# main.net
KiCad netlist of a schematic drawn in Altium Designer
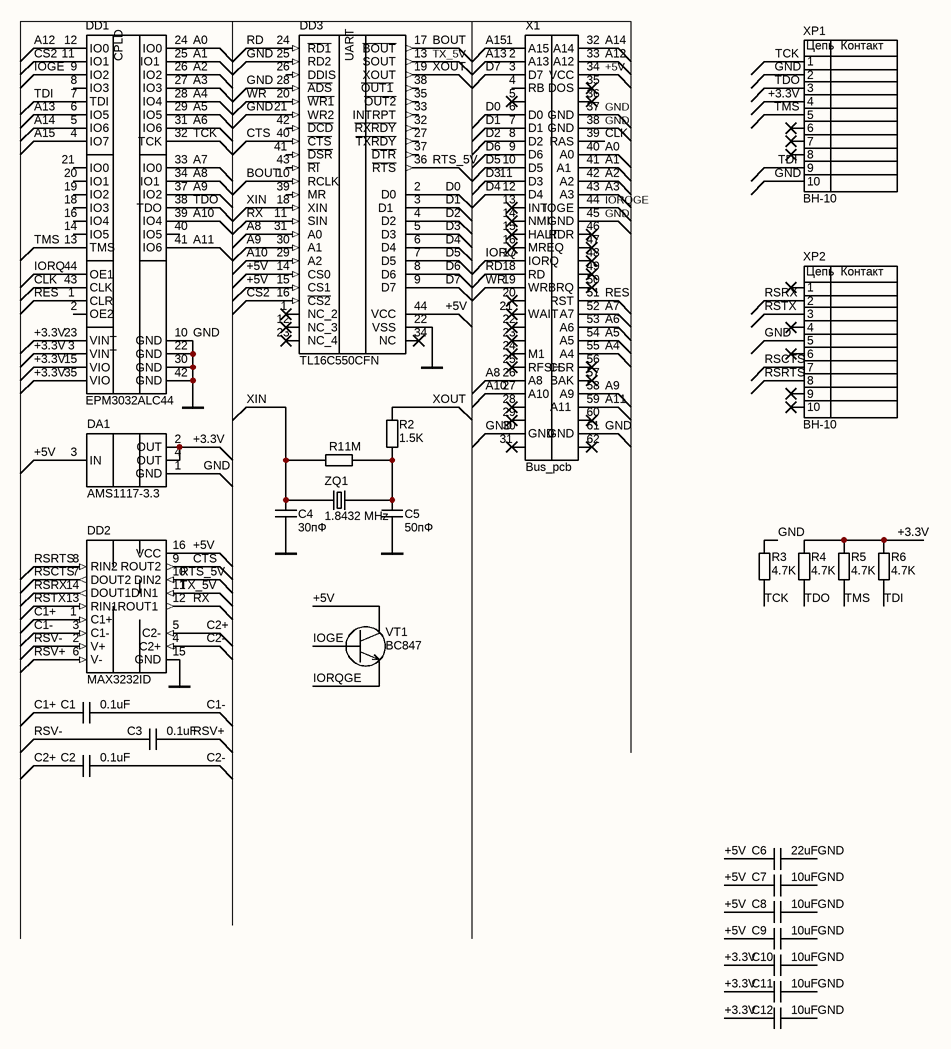
[diagram p0: main.SchDoc]

(export (version "E")
  (design (tool "Eeschema 10.0.6"))
  (components
    (comp (ref "C1") (value "0.1uF") (footprint "C0805") (libsource (lib "Capacitors") (part "CapCer")))
    (comp (ref "C2") (value "0.1uF") (footprint "C0805") (libsource (lib "Capacitors") (part "CapCer")))
    (comp (ref "C3") (value "0.1uF") (footprint "C0805") (libsource (lib "Capacitors") (part "CapCer")))
    (comp (ref "C4") (value "30пФ") (footprint "C0805") (libsource (lib "Capacitors") (part "CapCer")))
    (comp (ref "C5") (value "50пФ") (footprint "C0805") (libsource (lib "Capacitors") (part "CapCer")))
    (comp (ref "C6") (value "22uF") (footprint "С1206") (libsource (lib "Capacitors") (part "CapCer")))
    (comp (ref "C7") (value "10uF") (footprint "C0805") (libsource (lib "Capacitors") (part "CapCer")))
    (comp (ref "C8") (value "10uF") (footprint "C0805") (libsource (lib "Capacitors") (part "CapCer")))
    (comp (ref "C9") (value "10uF") (footprint "C0805") (libsource (lib "Capacitors") (part "CapCer")))
    (comp (ref "C10") (value "10uF") (footprint "C0805") (libsource (lib "Capacitors") (part "CapCer")))
    (comp (ref "C11") (value "10uF") (footprint "C0805") (libsource (lib "Capacitors") (part "CapCer")))
    (comp (ref "C12") (value "10uF") (footprint "C0805") (libsource (lib "Capacitors") (part "CapCer")))
    (comp (ref "DA1")
      (value "AMS1117-3.3")
      (footprint "SOT229P700X180-4N")
      (libsource (lib "LDO") (part "AMS1117-3.3"))
    )
    (comp (ref "DD1")
      (value "EPM3032ALC44")
      (footprint "PLCC-44-R")
      (description "44-Pin PLCC44")
      (libsource (lib "cpld") (part "EPM3032ALC44"))
    )
    (comp (ref "DD2")
      (value "MAX3232ID")
      (footprint "SOIC127P600X175-16N")
      (description "3-V to 5.5-V multichannel RS-232 line driver & receiver 16-SOIC -40 to 85")
      (fields (field (name "MF") "Texas Instruments"))
      (libsource (lib "Shifter") (part "MAX3232ID"))
    )
    (comp (ref "DD3")
      (value "TL16C550CFN")
      (footprint "PLCC-44-R")
      (description "ASYNCHRONOUS COMMUNICATIONS ELEMENT")
      (libsource (lib "uart") (part "TL16C550CFN"))
    )
    (comp (ref "R1") (value "1M") (footprint "R0805") (libsource (lib "Resistors") (part "Res")))
    (comp (ref "R2") (value "1.5K") (footprint "R0805") (libsource (lib "Resistors") (part "Res")))
    (comp (ref "R3") (value "4.7K") (footprint "R0805") (libsource (lib "Resistors") (part "Res")))
    (comp (ref "R4") (value "4.7K") (footprint "R0805") (libsource (lib "Resistors") (part "Res")))
    (comp (ref "R5") (value "4.7K") (footprint "R0805") (libsource (lib "Resistors") (part "Res")))
    (comp (ref "R6") (value "4.7K") (footprint "R0805") (libsource (lib "Resistors") (part "Res")))
    (comp (ref "VT1")
      (value "BC847")
      (footprint "BC847")
      (description "NPN Transistor")
      (libsource (lib "Transistors") (part "BC847"))
    )
    (comp (ref "X1") (value "Bus_pcb") (footprint "BUS") (libsource (lib "Connectors") (part "Bus_pcb")))
    (comp (ref "XP1")
      (value "BH-10")
      (footprint "BH-10")
      (description "10 Position Total Dual Row 2.54 mm Pitch Straight Male Shrouded Box Header")
      (fields (field (name "MF") "Sullins Connector") (field (name "MP") "SBH11-PBPC-D05-ST-BK"))
      (libsource (lib "Connectors") (part "BH-10"))
    )
    (comp (ref "XP2")
      (value "BH-10")
      (footprint "BH-10")
      (description "10 Position Total Dual Row 2.54 mm Pitch Straight Male Shrouded Box Header")
      (fields (field (name "MF") "Sullins Connector") (field (name "MP") "SBH11-PBPC-D05-ST-BK"))
      (libsource (lib "Connectors") (part "BH-10"))
    )
    (comp (ref "ZQ1")
      (value "1.8432 MHz")
      (footprint "XTAL_HC-49U")
      (libsource (lib "Oscillators") (part "HC-49U_1.8432"))
    )
  )
  (nets
    (net (code "1") (name "/+3.3V") (class "Default")
      (node (ref "C10") (pin "1") (pinfunction "1_1") (pintype "passive"))
      (node (ref "C11") (pin "1") (pinfunction "1_1") (pintype "passive"))
      (node (ref "C12") (pin "1") (pinfunction "1_1") (pintype "passive"))
      (node (ref "DA1") (pin "2") (pinfunction "OUT_2") (pintype "passive"))
      (node (ref "DA1") (pin "4") (pinfunction "OUT_4") (pintype "passive"))
      (node (ref "DD1") (pin "15") (pinfunction "VIO_15") (pintype "passive"))
      (node (ref "DD1") (pin "23") (pinfunction "VINT_23") (pintype "passive"))
      (node (ref "DD1") (pin "3") (pinfunction "VINT_3") (pintype "passive"))
      (node (ref "DD1") (pin "35") (pinfunction "VIO_35") (pintype "passive"))
      (node (ref "R4") (pin "2") (pinfunction "2_2") (pintype "passive"))
      (node (ref "R5") (pin "2") (pinfunction "2_2") (pintype "passive"))
      (node (ref "R6") (pin "2") (pinfunction "2_2") (pintype "passive"))
      (node (ref "XP1") (pin "4") (pinfunction "4_4") (pintype "passive"))
    )
    (net (code "2") (name "/+5V") (class "Default")
      (node (ref "C6") (pin "1") (pinfunction "1_1") (pintype "passive"))
      (node (ref "C7") (pin "1") (pinfunction "1_1") (pintype "passive"))
      (node (ref "C8") (pin "1") (pinfunction "1_1") (pintype "passive"))
      (node (ref "C9") (pin "1") (pinfunction "1_1") (pintype "passive"))
      (node (ref "DA1") (pin "3") (pinfunction "IN_3") (pintype "passive"))
      (node (ref "DD2") (pin "16") (pinfunction "VCC_16") (pintype "power_in"))
      (node (ref "DD3") (pin "14") (pinfunction "CS0_14") (pintype "input"))
      (node (ref "DD3") (pin "15") (pinfunction "CS1_15") (pintype "input"))
      (node (ref "DD3") (pin "44") (pinfunction "VCC_44") (pintype "power_in"))
      (node (ref "VT1") (pin "3") (pinfunction "C_3") (pintype "power_in"))
      (node (ref "X1") (pin "34") (pinfunction "VCC_34") (pintype "passive"))
    )
    (net (code "3") (name "/A0") (class "Default")
      (node (ref "DD1") (pin "24") (pinfunction "IO0_24") (pintype "passive"))
      (node (ref "X1") (pin "40") (pinfunction "A0_40") (pintype "passive"))
    )
    (net (code "4") (name "/A1") (class "Default")
      (node (ref "DD1") (pin "25") (pinfunction "IO1_25") (pintype "passive"))
      (node (ref "X1") (pin "41") (pinfunction "A1_41") (pintype "passive"))
    )
    (net (code "5") (name "/A2") (class "Default")
      (node (ref "DD1") (pin "26") (pinfunction "IO2_26") (pintype "passive"))
      (node (ref "X1") (pin "42") (pinfunction "A2_42") (pintype "passive"))
    )
    (net (code "6") (name "/A3") (class "Default")
      (node (ref "DD1") (pin "27") (pinfunction "IO3_27") (pintype "passive"))
      (node (ref "X1") (pin "43") (pinfunction "A3_43") (pintype "passive"))
    )
    (net (code "7") (name "/A4") (class "Default")
      (node (ref "DD1") (pin "28") (pinfunction "IO4_28") (pintype "passive"))
      (node (ref "X1") (pin "55") (pinfunction "A4_55") (pintype "passive"))
    )
    (net (code "8") (name "/A5") (class "Default")
      (node (ref "DD1") (pin "29") (pinfunction "IO5_29") (pintype "passive"))
      (node (ref "X1") (pin "54") (pinfunction "A5_54") (pintype "passive"))
    )
    (net (code "9") (name "/A6") (class "Default")
      (node (ref "DD1") (pin "31") (pinfunction "IO6_31") (pintype "passive"))
      (node (ref "X1") (pin "53") (pinfunction "A6_53") (pintype "passive"))
    )
    (net (code "10") (name "/A7") (class "Default")
      (node (ref "DD1") (pin "33") (pinfunction "IO0_33") (pintype "passive"))
      (node (ref "X1") (pin "52") (pinfunction "A7_52") (pintype "passive"))
    )
    (net (code "11") (name "/A8") (class "Default")
      (node (ref "DD1") (pin "34") (pinfunction "IO1_34") (pintype "passive"))
      (node (ref "DD3") (pin "31") (pinfunction "A0_31") (pintype "input"))
      (node (ref "X1") (pin "26") (pinfunction "A8_26") (pintype "passive"))
    )
    (net (code "12") (name "/A9") (class "Default")
      (node (ref "DD1") (pin "37") (pinfunction "IO2_37") (pintype "passive"))
      (node (ref "DD3") (pin "30") (pinfunction "A1_30") (pintype "input"))
      (node (ref "X1") (pin "58") (pinfunction "A9_58") (pintype "passive"))
    )
    (net (code "13") (name "/A10") (class "Default")
      (node (ref "DD1") (pin "39") (pinfunction "IO4_39") (pintype "passive"))
      (node (ref "DD3") (pin "29") (pinfunction "A2_29") (pintype "input"))
      (node (ref "X1") (pin "27") (pinfunction "A10_27") (pintype "passive"))
    )
    (net (code "14") (name "/A11") (class "Default")
      (node (ref "DD1") (pin "41") (pinfunction "IO6_41") (pintype "passive"))
      (node (ref "X1") (pin "59") (pinfunction "A11_59") (pintype "passive"))
    )
    (net (code "15") (name "/A12") (class "Default")
      (node (ref "DD1") (pin "12") (pinfunction "IO0_12") (pintype "passive"))
      (node (ref "X1") (pin "33") (pinfunction "A12_33") (pintype "passive"))
    )
    (net (code "16") (name "/A13") (class "Default")
      (node (ref "DD1") (pin "6") (pinfunction "IO5_6") (pintype "passive"))
      (node (ref "X1") (pin "2") (pinfunction "A13_2") (pintype "passive"))
    )
    (net (code "17") (name "/A14") (class "Default")
      (node (ref "DD1") (pin "5") (pinfunction "IO6_5") (pintype "passive"))
      (node (ref "X1") (pin "32") (pinfunction "A14_32") (pintype "passive"))
    )
    (net (code "18") (name "/A15") (class "Default")
      (node (ref "DD1") (pin "4") (pinfunction "IO7_4") (pintype "passive"))
      (node (ref "X1") (pin "1") (pinfunction "A15_1") (pintype "passive"))
    )
    (net (code "19") (name "/BOUT") (class "Default")
      (node (ref "DD3") (pin "10") (pinfunction "RCLK_10") (pintype "input"))
      (node (ref "DD3") (pin "17") (pinfunction "~{BOUT}_17") (pintype "output"))
    )
    (net (code "20") (name "/C1+") (class "Default")
      (node (ref "C1") (pin "1") (pinfunction "1_1") (pintype "passive"))
      (node (ref "DD2") (pin "1") (pinfunction "C1+_1") (pintype "input"))
    )
    (net (code "21") (name "/C1-") (class "Default")
      (node (ref "C1") (pin "2") (pinfunction "2_2") (pintype "passive"))
      (node (ref "DD2") (pin "3") (pinfunction "C1-_3") (pintype "input"))
    )
    (net (code "22") (name "/C2+") (class "Default")
      (node (ref "C2") (pin "1") (pinfunction "1_1") (pintype "passive"))
      (node (ref "DD2") (pin "5") (pinfunction "C2-_5") (pintype "input"))
    )
    (net (code "23") (name "/C2-") (class "Default")
      (node (ref "C2") (pin "2") (pinfunction "2_2") (pintype "passive"))
      (node (ref "DD2") (pin "4") (pinfunction "C2+_4") (pintype "input"))
    )
    (net (code "24") (name "/CLK") (class "Default")
      (node (ref "DD1") (pin "43") (pinfunction "CLK_43") (pintype "passive"))
      (node (ref "X1") (pin "39") (pinfunction "RAS_39") (pintype "passive"))
    )
    (net (code "25") (name "/CS2") (class "Default")
      (node (ref "DD1") (pin "11") (pinfunction "IO1_11") (pintype "passive"))
      (node (ref "DD3") (pin "16") (pinfunction "~{CS2}_16") (pintype "input"))
    )
    (net (code "26") (name "/CTS") (class "Default")
      (node (ref "DD2") (pin "9") (pinfunction "ROUT2_9") (pintype "output"))
      (node (ref "DD3") (pin "40") (pinfunction "~{CTS}_40") (pintype "input"))
    )
    (net (code "27") (name "/D0") (class "Default")
      (node (ref "DD3") (pin "2") (pinfunction "D0_2") (pintype "bidirectional"))
      (node (ref "X1") (pin "6") (pinfunction "D0_6") (pintype "passive"))
    )
    (net (code "28") (name "/D1") (class "Default")
      (node (ref "DD3") (pin "3") (pinfunction "D1_3") (pintype "bidirectional"))
      (node (ref "X1") (pin "7") (pinfunction "D1_7") (pintype "passive"))
    )
    (net (code "29") (name "/D2") (class "Default")
      (node (ref "DD3") (pin "4") (pinfunction "D2_4") (pintype "bidirectional"))
      (node (ref "X1") (pin "8") (pinfunction "D2_8") (pintype "passive"))
    )
    (net (code "30") (name "/D3") (class "Default")
      (node (ref "DD3") (pin "5") (pinfunction "D3_5") (pintype "bidirectional"))
      (node (ref "X1") (pin "11") (pinfunction "D3_11") (pintype "passive"))
    )
    (net (code "31") (name "/D4") (class "Default")
      (node (ref "DD3") (pin "6") (pinfunction "D4_6") (pintype "bidirectional"))
      (node (ref "X1") (pin "12") (pinfunction "D4_12") (pintype "passive"))
    )
    (net (code "32") (name "/D5") (class "Default")
      (node (ref "DD3") (pin "7") (pinfunction "D5_7") (pintype "bidirectional"))
      (node (ref "X1") (pin "10") (pinfunction "D5_10") (pintype "passive"))
    )
    (net (code "33") (name "/D6") (class "Default")
      (node (ref "DD3") (pin "8") (pinfunction "D6_8") (pintype "bidirectional"))
      (node (ref "X1") (pin "9") (pinfunction "D6_9") (pintype "passive"))
    )
    (net (code "34") (name "/D7") (class "Default")
      (node (ref "DD3") (pin "9") (pinfunction "D7_9") (pintype "bidirectional"))
      (node (ref "X1") (pin "3") (pinfunction "D7_3") (pintype "passive"))
    )
    (net (code "35") (name "/IOGE") (class "Default")
      (node (ref "DD1") (pin "9") (pinfunction "IO2_9") (pintype "passive"))
      (node (ref "VT1") (pin "1") (pinfunction "B_1") (pintype "power_in"))
    )
    (net (code "36") (name "/IORQ") (class "Default")
      (node (ref "DD1") (pin "44") (pinfunction "OE1_44") (pintype "passive"))
      (node (ref "X1") (pin "17") (pinfunction "IORQ_17") (pintype "passive"))
    )
    (net (code "37") (name "/IORQGE") (class "Default")
      (node (ref "VT1") (pin "2") (pinfunction "E_2") (pintype "power_in"))
      (node (ref "X1") (pin "44") (pinfunction "IOGE_44") (pintype "passive"))
    )
    (net (code "38") (name "/RD") (class "Default")
      (node (ref "DD3") (pin "24") (pinfunction "~{RD1}_24") (pintype "input"))
      (node (ref "X1") (pin "18") (pinfunction "RD_18") (pintype "passive"))
    )
    (net (code "39") (name "/RES") (class "Default")
      (node (ref "DD1") (pin "1") (pinfunction "CLR_1") (pintype "passive"))
      (node (ref "X1") (pin "51") (pinfunction "RST_51") (pintype "passive"))
    )
    (net (code "40") (name "/RSCTS") (class "Default")
      (node (ref "DD2") (pin "7") (pinfunction "DOUT2_7") (pintype "output"))
      (node (ref "XP2") (pin "7") (pinfunction "7_7") (pintype "passive"))
    )
    (net (code "41") (name "/RSRTS") (class "Default")
      (node (ref "DD2") (pin "8") (pinfunction "RIN2_8") (pintype "input"))
      (node (ref "XP2") (pin "8") (pinfunction "8_8") (pintype "passive"))
    )
    (net (code "42") (name "/RSRX") (class "Default")
      (node (ref "DD2") (pin "14") (pinfunction "DOUT1_14") (pintype "output"))
      (node (ref "XP2") (pin "2") (pinfunction "2_2") (pintype "passive"))
    )
    (net (code "43") (name "/RSTX") (class "Default")
      (node (ref "DD2") (pin "13") (pinfunction "RIN1_13") (pintype "input"))
      (node (ref "XP2") (pin "3") (pinfunction "3_3") (pintype "passive"))
    )
    (net (code "44") (name "/RSV+") (class "Default")
      (node (ref "C3") (pin "2") (pinfunction "2_2") (pintype "passive"))
      (node (ref "DD2") (pin "6") (pinfunction "V-_6") (pintype "input"))
    )
    (net (code "45") (name "/RSV-") (class "Default")
      (node (ref "C3") (pin "1") (pinfunction "1_1") (pintype "passive"))
      (node (ref "DD2") (pin "2") (pinfunction "V+_2") (pintype "input"))
    )
    (net (code "46") (name "/RTS_5V") (class "Default")
      (node (ref "DD2") (pin "10") (pinfunction "DIN2_10") (pintype "input"))
      (node (ref "DD3") (pin "36") (pinfunction "~{RTS}_36") (pintype "output"))
    )
    (net (code "47") (name "/RX") (class "Default")
      (node (ref "DD2") (pin "12") (pinfunction "ROUT1_12") (pintype "output"))
      (node (ref "DD3") (pin "11") (pinfunction "SIN_11") (pintype "input"))
    )
    (net (code "48") (name "/TCK") (class "Default")
      (node (ref "DD1") (pin "32") (pinfunction "TCK_32") (pintype "passive"))
      (node (ref "R3") (pin "1") (pinfunction "1_1") (pintype "passive"))
      (node (ref "XP1") (pin "1") (pinfunction "1_1") (pintype "passive"))
    )
    (net (code "49") (name "/TDI") (class "Default")
      (node (ref "DD1") (pin "7") (pinfunction "TDI_7") (pintype "passive"))
      (node (ref "R6") (pin "1") (pinfunction "1_1") (pintype "passive"))
      (node (ref "XP1") (pin "9") (pinfunction "9_9") (pintype "passive"))
    )
    (net (code "50") (name "/TDO") (class "Default")
      (node (ref "DD1") (pin "38") (pinfunction "TDO_38") (pintype "passive"))
      (node (ref "R4") (pin "1") (pinfunction "1_1") (pintype "passive"))
      (node (ref "XP1") (pin "3") (pinfunction "3_3") (pintype "passive"))
    )
    (net (code "51") (name "/TMS") (class "Default")
      (node (ref "DD1") (pin "13") (pinfunction "TMS_13") (pintype "passive"))
      (node (ref "R5") (pin "1") (pinfunction "1_1") (pintype "passive"))
      (node (ref "XP1") (pin "5") (pinfunction "5_5") (pintype "passive"))
    )
    (net (code "52") (name "/TX_5V") (class "Default")
      (node (ref "DD2") (pin "11") (pinfunction "DIN1_11") (pintype "input"))
      (node (ref "DD3") (pin "13") (pinfunction "SOUT_13") (pintype "output"))
    )
    (net (code "53") (name "/WR") (class "Default")
      (node (ref "DD3") (pin "20") (pinfunction "~{WR1}_20") (pintype "input"))
      (node (ref "X1") (pin "19") (pinfunction "WR_19") (pintype "passive"))
    )
    (net (code "54") (name "/XIN") (class "Default")
      (node (ref "C4") (pin "2") (pinfunction "2_2") (pintype "passive"))
      (node (ref "DD3") (pin "18") (pinfunction "XIN_18") (pintype "input"))
      (node (ref "R1") (pin "1") (pinfunction "1_1") (pintype "passive"))
      (node (ref "ZQ1") (pin "1") (pinfunction "1_1") (pintype "passive"))
    )
    (net (code "55") (name "/XOUT") (class "Default")
      (node (ref "DD3") (pin "19") (pinfunction "XOUT_19") (pintype "output"))
      (node (ref "R2") (pin "2") (pinfunction "2_2") (pintype "passive"))
    )
    (net (code "56") (name "GND") (class "Default")
      (node (ref "C10") (pin "2") (pinfunction "2_2") (pintype "passive"))
      (node (ref "C11") (pin "2") (pinfunction "2_2") (pintype "passive"))
      (node (ref "C12") (pin "2") (pinfunction "2_2") (pintype "passive"))
      (node (ref "C4") (pin "1") (pinfunction "1_1") (pintype "passive"))
      (node (ref "C5") (pin "1") (pinfunction "1_1") (pintype "passive"))
      (node (ref "C6") (pin "2") (pinfunction "2_2") (pintype "passive"))
      (node (ref "C7") (pin "2") (pinfunction "2_2") (pintype "passive"))
      (node (ref "C8") (pin "2") (pinfunction "2_2") (pintype "passive"))
      (node (ref "C9") (pin "2") (pinfunction "2_2") (pintype "passive"))
      (node (ref "DA1") (pin "1") (pinfunction "GND_1") (pintype "passive"))
      (node (ref "DD1") (pin "10") (pinfunction "GND_10") (pintype "passive"))
      (node (ref "DD1") (pin "22") (pinfunction "GND_22") (pintype "passive"))
      (node (ref "DD1") (pin "30") (pinfunction "GND_30") (pintype "passive"))
      (node (ref "DD1") (pin "42") (pinfunction "GND_42") (pintype "passive"))
      (node (ref "DD2") (pin "15") (pinfunction "GND_15") (pintype "power_in"))
      (node (ref "DD3") (pin "21") (pinfunction "WR2_21") (pintype "input"))
      (node (ref "DD3") (pin "22") (pinfunction "VSS_22") (pintype "power_in"))
      (node (ref "DD3") (pin "25") (pinfunction "RD2_25") (pintype "input"))
      (node (ref "DD3") (pin "28") (pinfunction "~{ADS}_28") (pintype "input"))
      (node (ref "R3") (pin "2") (pinfunction "2_2") (pintype "passive"))
      (node (ref "X1") (pin "30") (pinfunction "GND_30") (pintype "passive"))
      (node (ref "X1") (pin "37") (pinfunction "GND_37") (pintype "passive"))
      (node (ref "X1") (pin "38") (pinfunction "GND_38") (pintype "passive"))
      (node (ref "X1") (pin "45") (pinfunction "GND_45") (pintype "passive"))
      (node (ref "X1") (pin "61") (pinfunction "GND_61") (pintype "passive"))
      (node (ref "XP1") (pin "10") (pinfunction "10_10") (pintype "passive"))
      (node (ref "XP1") (pin "2") (pinfunction "2_2") (pintype "passive"))
      (node (ref "XP2") (pin "5") (pinfunction "5_5") (pintype "passive"))
    )
    (net (code "57") (name "Net-(C5-Pad2)") (class "Default")
      (node (ref "C5") (pin "2") (pinfunction "2_2") (pintype "passive"))
      (node (ref "R1") (pin "2") (pinfunction "2_2") (pintype "passive"))
      (node (ref "R2") (pin "1") (pinfunction "1_1") (pintype "passive"))
      (node (ref "ZQ1") (pin "2") (pinfunction "2_2") (pintype "passive"))
    )
    (net (code "58") (name "unconnected-(DD1-IO0-Pad21)") (class "Default")
      (node (ref "DD1") (pin "21") (pinfunction "IO0_21") (pintype "passive"))
    )
    (net (code "59") (name "unconnected-(DD1-IO1-Pad20)") (class "Default")
      (node (ref "DD1") (pin "20") (pinfunction "IO1_20") (pintype "passive"))
    )
    (net (code "60") (name "unconnected-(DD1-IO2-Pad19)") (class "Default")
      (node (ref "DD1") (pin "19") (pinfunction "IO2_19") (pintype "passive"))
    )
    (net (code "61") (name "unconnected-(DD1-IO3-Pad8)") (class "Default")
      (node (ref "DD1") (pin "8") (pinfunction "IO3_8") (pintype "passive"))
    )
    (net (code "62") (name "unconnected-(DD1-IO3-Pad18)") (class "Default")
      (node (ref "DD1") (pin "18") (pinfunction "IO3_18") (pintype "passive"))
    )
    (net (code "63") (name "unconnected-(DD1-IO4-Pad16)") (class "Default")
      (node (ref "DD1") (pin "16") (pinfunction "IO4_16") (pintype "passive"))
    )
    (net (code "64") (name "unconnected-(DD1-IO5-Pad14)") (class "Default")
      (node (ref "DD1") (pin "14") (pinfunction "IO5_14") (pintype "passive"))
    )
    (net (code "65") (name "unconnected-(DD1-IO5-Pad40)") (class "Default")
      (node (ref "DD1") (pin "40") (pinfunction "IO5_40") (pintype "passive"))
    )
    (net (code "66") (name "unconnected-(DD1-OE2-Pad2)") (class "Default")
      (node (ref "DD1") (pin "2") (pinfunction "OE2_2") (pintype "passive"))
    )
    (net (code "67") (name "unconnected-(DD3-DDIS-Pad26)") (class "Default")
      (node (ref "DD3") (pin "26") (pinfunction "DDIS_26") (pintype "input"))
    )
    (net (code "68") (name "unconnected-(DD3-INTRPT-Pad33)") (class "Default")
      (node (ref "DD3") (pin "33") (pinfunction "INTRPT_33") (pintype "output"))
    )
    (net (code "69") (name "unconnected-(DD3-MR-Pad39)") (class "Default")
      (node (ref "DD3") (pin "39") (pinfunction "MR_39") (pintype "input"))
    )
    (net (code "70") (name "unconnected-(DD3-NC-Pad34)") (class "Default")
      (node (ref "DD3") (pin "34") (pinfunction "NC_34") (pintype "passive+no_connect"))
    )
    (net (code "71") (name "unconnected-(DD3-NC_2-Pad1)") (class "Default")
      (node (ref "DD3") (pin "1") (pinfunction "NC_2_1") (pintype "passive+no_connect"))
    )
    (net (code "72") (name "unconnected-(DD3-NC_3-Pad12)") (class "Default")
      (node (ref "DD3") (pin "12") (pinfunction "NC_3_12") (pintype "passive+no_connect"))
    )
    (net (code "73") (name "unconnected-(DD3-NC_4-Pad23)") (class "Default")
      (node (ref "DD3") (pin "23") (pinfunction "NC_4_23") (pintype "passive+no_connect"))
    )
    (net (code "74") (name "unconnected-(DD3-~{DCD}-Pad42)") (class "Default")
      (node (ref "DD3") (pin "42") (pinfunction "~{DCD}_42") (pintype "input"))
    )
    (net (code "75") (name "unconnected-(DD3-~{DSR}-Pad41)") (class "Default")
      (node (ref "DD3") (pin "41") (pinfunction "~{DSR}_41") (pintype "input"))
    )
    (net (code "76") (name "unconnected-(DD3-~{DTR}-Pad37)") (class "Default")
      (node (ref "DD3") (pin "37") (pinfunction "~{DTR}_37") (pintype "output"))
    )
    (net (code "77") (name "unconnected-(DD3-~{OUT1}-Pad38)") (class "Default")
      (node (ref "DD3") (pin "38") (pinfunction "~{OUT1}_38") (pintype "output"))
    )
    (net (code "78") (name "unconnected-(DD3-~{OUT2}-Pad35)") (class "Default")
      (node (ref "DD3") (pin "35") (pinfunction "~{OUT2}_35") (pintype "output"))
    )
    (net (code "79") (name "unconnected-(DD3-~{RI}-Pad43)") (class "Default")
      (node (ref "DD3") (pin "43") (pinfunction "~{RI}_43") (pintype "input"))
    )
    (net (code "80") (name "unconnected-(DD3-~{RXRDY}-Pad32)") (class "Default")
      (node (ref "DD3") (pin "32") (pinfunction "~{RXRDY}_32") (pintype "output"))
    )
    (net (code "81") (name "unconnected-(DD3-~{TXRDY}-Pad27)") (class "Default")
      (node (ref "DD3") (pin "27") (pinfunction "~{TXRDY}_27") (pintype "output"))
    )
    (net (code "82") (name "unconnected-(X1-BAK-Pad57)") (class "Default")
      (node (ref "X1") (pin "57") (pinfunction "BAK_57") (pintype "passive+no_connect"))
    )
    (net (code "83") (name "unconnected-(X1-BRQ-Pad50)") (class "Default")
      (node (ref "X1") (pin "50") (pinfunction "BRQ_50") (pintype "passive+no_connect"))
    )
    (net (code "84") (name "unconnected-(X1-CSR-Pad56)") (class "Default")
      (node (ref "X1") (pin "56") (pinfunction "CSR_56") (pintype "passive+no_connect"))
    )
    (net (code "85") (name "unconnected-(X1-DOS-Pad35)") (class "Default")
      (node (ref "X1") (pin "35") (pinfunction "DOS_35") (pintype "passive+no_connect"))
    )
    (net (code "86") (name "unconnected-(X1-HALT-Pad15)") (class "Default")
      (node (ref "X1") (pin "15") (pinfunction "HALT_15") (pintype "passive+no_connect"))
    )
    (net (code "87") (name "unconnected-(X1-INT-Pad13)") (class "Default")
      (node (ref "X1") (pin "13") (pinfunction "INT_13") (pintype "passive+no_connect"))
    )
    (net (code "88") (name "unconnected-(X1-M1-Pad24)") (class "Default")
      (node (ref "X1") (pin "24") (pinfunction "M1_24") (pintype "passive+no_connect"))
    )
    (net (code "89") (name "unconnected-(X1-MREQ-Pad16)") (class "Default")
      (node (ref "X1") (pin "16") (pinfunction "MREQ_16") (pintype "passive+no_connect"))
    )
    (net (code "90") (name "unconnected-(X1-NMI-Pad14)") (class "Default")
      (node (ref "X1") (pin "14") (pinfunction "NMI_14") (pintype "passive+no_connect"))
    )
    (net (code "91") (name "unconnected-(X1-Pad5)") (class "Default")
      (node (ref "X1") (pin "5") (pintype "passive+no_connect"))
    )
    (net (code "92") (name "unconnected-(X1-Pad20)") (class "Default")
      (node (ref "X1") (pin "20") (pintype "passive+no_connect"))
    )
    (net (code "93") (name "unconnected-(X1-Pad22)") (class "Default")
      (node (ref "X1") (pin "22") (pintype "passive+no_connect"))
    )
    (net (code "94") (name "unconnected-(X1-Pad23)") (class "Default")
      (node (ref "X1") (pin "23") (pintype "passive+no_connect"))
    )
    (net (code "95") (name "unconnected-(X1-Pad28)") (class "Default")
      (node (ref "X1") (pin "28") (pintype "passive+no_connect"))
    )
    (net (code "96") (name "unconnected-(X1-Pad29)") (class "Default")
      (node (ref "X1") (pin "29") (pintype "passive+no_connect"))
    )
    (net (code "97") (name "unconnected-(X1-Pad31)") (class "Default")
      (node (ref "X1") (pin "31") (pintype "passive+no_connect"))
    )
    (net (code "98") (name "unconnected-(X1-Pad36)") (class "Default")
      (node (ref "X1") (pin "36") (pintype "passive+no_connect"))
    )
    (net (code "99") (name "unconnected-(X1-Pad47)") (class "Default")
      (node (ref "X1") (pin "47") (pintype "passive+no_connect"))
    )
    (net (code "100") (name "unconnected-(X1-Pad48)") (class "Default")
      (node (ref "X1") (pin "48") (pintype "passive+no_connect"))
    )
    (net (code "101") (name "unconnected-(X1-Pad49)") (class "Default")
      (node (ref "X1") (pin "49") (pintype "passive+no_connect"))
    )
    (net (code "102") (name "unconnected-(X1-Pad60)") (class "Default")
      (node (ref "X1") (pin "60") (pintype "passive+no_connect"))
    )
    (net (code "103") (name "unconnected-(X1-Pad62)") (class "Default")
      (node (ref "X1") (pin "62") (pintype "passive+no_connect"))
    )
    (net (code "104") (name "unconnected-(X1-RB-Pad4)") (class "Default")
      (node (ref "X1") (pin "4") (pinfunction "RB_4") (pintype "passive"))
    )
    (net (code "105") (name "unconnected-(X1-RDR-Pad46)") (class "Default")
      (node (ref "X1") (pin "46") (pinfunction "RDR_46") (pintype "passive+no_connect"))
    )
    (net (code "106") (name "unconnected-(X1-RFSH-Pad25)") (class "Default")
      (node (ref "X1") (pin "25") (pinfunction "RFSH_25") (pintype "passive+no_connect"))
    )
    (net (code "107") (name "unconnected-(X1-WAIT-Pad21)") (class "Default")
      (node (ref "X1") (pin "21") (pinfunction "WAIT_21") (pintype "passive+no_connect"))
    )
    (net (code "108") (name "unconnected-(XP1-Pad6)") (class "Default")
      (node (ref "XP1") (pin "6") (pinfunction "6_6") (pintype "passive+no_connect"))
    )
    (net (code "109") (name "unconnected-(XP1-Pad7)") (class "Default")
      (node (ref "XP1") (pin "7") (pinfunction "7_7") (pintype "passive+no_connect"))
    )
    (net (code "110") (name "unconnected-(XP1-Pad8)") (class "Default")
      (node (ref "XP1") (pin "8") (pinfunction "8_8") (pintype "passive+no_connect"))
    )
    (net (code "111") (name "unconnected-(XP2-Pad1)") (class "Default")
      (node (ref "XP2") (pin "1") (pinfunction "1_1") (pintype "passive+no_connect"))
    )
    (net (code "112") (name "unconnected-(XP2-Pad4)") (class "Default")
      (node (ref "XP2") (pin "4") (pinfunction "4_4") (pintype "passive+no_connect"))
    )
    (net (code "113") (name "unconnected-(XP2-Pad6)") (class "Default")
      (node (ref "XP2") (pin "6") (pinfunction "6_6") (pintype "passive+no_connect"))
    )
    (net (code "114") (name "unconnected-(XP2-Pad9)") (class "Default")
      (node (ref "XP2") (pin "9") (pinfunction "9_9") (pintype "passive+no_connect"))
    )
    (net (code "115") (name "unconnected-(XP2-Pad10)") (class "Default")
      (node (ref "XP2") (pin "10") (pinfunction "10_10") (pintype "passive+no_connect"))
    )
  )
)
